# 07_FPGA_HSIO_B2.net
KiCad netlist of a schematic drawn in Altium Designer
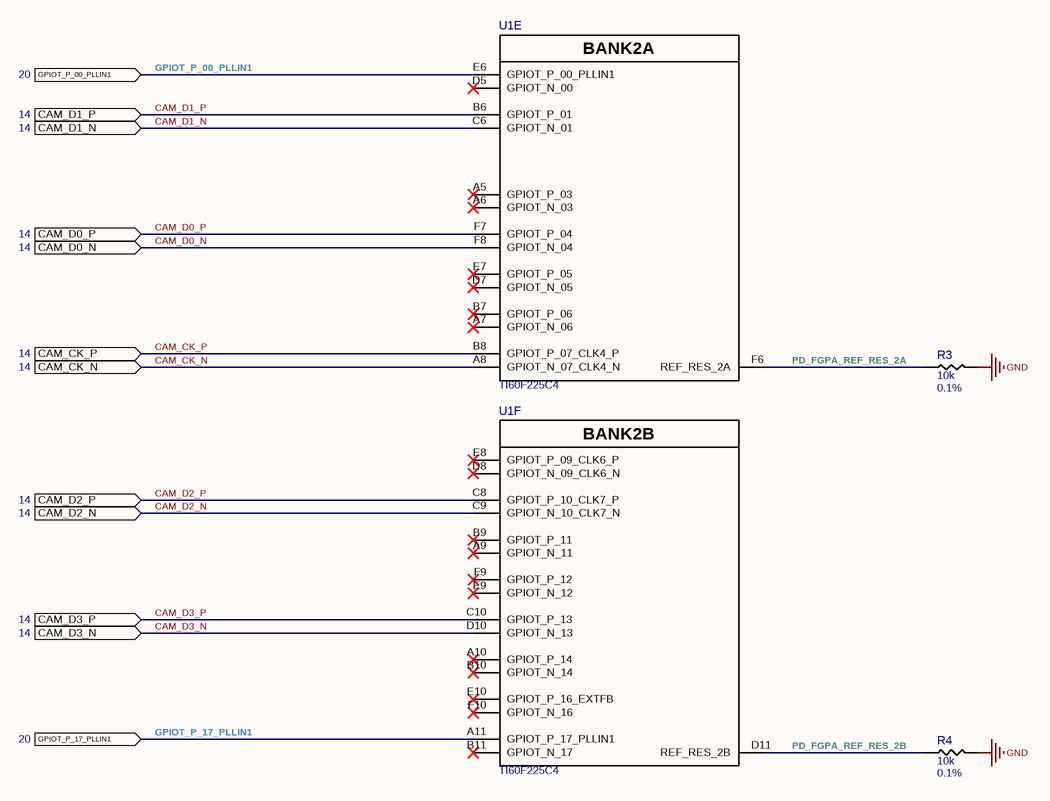
[diagram p0: 07_FPGA_HSIO_B2.SchDoc]

(export (version "E")
  (design (tool "Eeschema 10.0.6"))
  (components
    (comp (ref "R3")
      (value "10k")
      (footprint "RESC1005X03N")
      (description "RES SMD 10K OHM 0.1% 1/16W 0402")
      (fields (field (name "PART NUMBER") "RT0402BRD0710KL") (field (name "TOL") "0.1%"))
      (libsource (lib "Database") (part "Resistor_ENG"))
    )
    (comp (ref "R4")
      (value "10k")
      (footprint "RESC1005X03N")
      (description "RES SMD 10K OHM 0.1% 1/16W 0402")
      (fields (field (name "PART NUMBER") "RT0402BRD0710KL") (field (name "TOL") "0.1%"))
      (libsource (lib "Database") (part "Resistor_ENG"))
    )
    (comp (ref "U1")
      (value "TI60F225C4")
      (footprint "BGA225C65P15X15_1000X1000X100")
      (description "FPGA TITAN 140HSIO 4PLL 225BGA")
      (libsource (lib "Database") (part "TI60F225"))
    )
  )
  (nets
    (net (code "1") (name "/CAM_CK_N") (class "Default")
      (node (ref "U1") (pin "A8") (pinfunction "GPIOT_N_07_CLK4_N_A8") (pintype "passive"))
    )
    (net (code "2") (name "/CAM_CK_P") (class "Default")
      (node (ref "U1") (pin "B8") (pinfunction "GPIOT_P_07_CLK4_P_B8") (pintype "passive"))
    )
    (net (code "3") (name "/CAM_D0_N") (class "Default")
      (node (ref "U1") (pin "F8") (pinfunction "GPIOT_N_04_F8") (pintype "passive"))
    )
    (net (code "4") (name "/CAM_D0_P") (class "Default")
      (node (ref "U1") (pin "F7") (pinfunction "GPIOT_P_04_F7") (pintype "passive"))
    )
    (net (code "5") (name "/CAM_D1_N") (class "Default")
      (node (ref "U1") (pin "C6") (pinfunction "GPIOT_N_01_C6") (pintype "passive"))
    )
    (net (code "6") (name "/CAM_D1_P") (class "Default")
      (node (ref "U1") (pin "B6") (pinfunction "GPIOT_P_01_B6") (pintype "passive"))
    )
    (net (code "7") (name "/CAM_D2_N") (class "Default")
      (node (ref "U1") (pin "C9") (pinfunction "GPIOT_N_10_CLK7_N_C9") (pintype "passive"))
    )
    (net (code "8") (name "/CAM_D2_P") (class "Default")
      (node (ref "U1") (pin "C8") (pinfunction "GPIOT_P_10_CLK7_P_C8") (pintype "passive"))
    )
    (net (code "9") (name "/CAM_D3_N") (class "Default")
      (node (ref "U1") (pin "D10") (pinfunction "GPIOT_N_13_D10") (pintype "passive"))
    )
    (net (code "10") (name "/CAM_D3_P") (class "Default")
      (node (ref "U1") (pin "C10") (pinfunction "GPIOT_P_13_C10") (pintype "passive"))
    )
    (net (code "11") (name "/GPIOT_P_00_PLLIN1") (class "Default")
      (node (ref "U1") (pin "E6") (pinfunction "GPIOT_P_00_PLLIN1_E6") (pintype "passive"))
    )
    (net (code "12") (name "/GPIOT_P_17_PLLIN1") (class "Default")
      (node (ref "U1") (pin "A11") (pinfunction "GPIOT_P_17_PLLIN1_A11") (pintype "passive"))
    )
    (net (code "13") (name "/PD_FGPA_REF_RES_2A") (class "Default")
      (node (ref "R3") (pin "1") (pinfunction "1_1") (pintype "passive"))
      (node (ref "U1") (pin "F6") (pinfunction "REF_RES_2A_F6") (pintype "passive"))
    )
    (net (code "14") (name "/PD_FGPA_REF_RES_2B") (class "Default")
      (node (ref "R4") (pin "1") (pinfunction "1_1") (pintype "passive"))
      (node (ref "U1") (pin "D11") (pinfunction "REF_RES_2B_D11") (pintype "passive"))
    )
    (net (code "15") (name "GND") (class "Default")
      (node (ref "R3") (pin "2") (pinfunction "2_2") (pintype "passive"))
      (node (ref "R4") (pin "2") (pinfunction "2_2") (pintype "passive"))
    )
    (net (code "16") (name "unconnected-(U1E-GPIOT_N_00-PadD5)") (class "Default")
      (node (ref "U1") (pin "D5") (pinfunction "GPIOT_N_00_D5") (pintype "passive+no_connect"))
    )
    (net (code "17") (name "unconnected-(U1E-GPIOT_N_03-PadA6)") (class "Default")
      (node (ref "U1") (pin "A6") (pinfunction "GPIOT_N_03_A6") (pintype "passive+no_connect"))
    )
    (net (code "18") (name "unconnected-(U1E-GPIOT_N_05-PadD7)") (class "Default")
      (node (ref "U1") (pin "D7") (pinfunction "GPIOT_N_05_D7") (pintype "passive+no_connect"))
    )
    (net (code "19") (name "unconnected-(U1E-GPIOT_N_06-PadA7)") (class "Default")
      (node (ref "U1") (pin "A7") (pinfunction "GPIOT_N_06_A7") (pintype "passive+no_connect"))
    )
    (net (code "20") (name "unconnected-(U1E-GPIOT_P_03-PadA5)") (class "Default")
      (node (ref "U1") (pin "A5") (pinfunction "GPIOT_P_03_A5") (pintype "passive+no_connect"))
    )
    (net (code "21") (name "unconnected-(U1E-GPIOT_P_05-PadE7)") (class "Default")
      (node (ref "U1") (pin "E7") (pinfunction "GPIOT_P_05_E7") (pintype "passive+no_connect"))
    )
    (net (code "22") (name "unconnected-(U1E-GPIOT_P_06-PadB7)") (class "Default")
      (node (ref "U1") (pin "B7") (pinfunction "GPIOT_P_06_B7") (pintype "passive+no_connect"))
    )
    (net (code "23") (name "unconnected-(U1F-GPIOT_N_09_CLK6_N-PadD8)") (class "Default")
      (node (ref "U1") (pin "D8") (pinfunction "GPIOT_N_09_CLK6_N_D8") (pintype "passive+no_connect"))
    )
    (net (code "24") (name "unconnected-(U1F-GPIOT_N_11-PadA9)") (class "Default")
      (node (ref "U1") (pin "A9") (pinfunction "GPIOT_N_11_A9") (pintype "passive+no_connect"))
    )
    (net (code "25") (name "unconnected-(U1F-GPIOT_N_12-PadE9)") (class "Default")
      (node (ref "U1") (pin "E9") (pinfunction "GPIOT_N_12_E9") (pintype "passive+no_connect"))
    )
    (net (code "26") (name "unconnected-(U1F-GPIOT_N_14-PadB10)") (class "Default")
      (node (ref "U1") (pin "B10") (pinfunction "GPIOT_N_14_B10") (pintype "passive+no_connect"))
    )
    (net (code "27") (name "unconnected-(U1F-GPIOT_N_16-PadF10)") (class "Default")
      (node (ref "U1") (pin "F10") (pinfunction "GPIOT_N_16_F10") (pintype "passive+no_connect"))
    )
    (net (code "28") (name "unconnected-(U1F-GPIOT_N_17-PadB11)") (class "Default")
      (node (ref "U1") (pin "B11") (pinfunction "GPIOT_N_17_B11") (pintype "passive+no_connect"))
    )
    (net (code "29") (name "unconnected-(U1F-GPIOT_P_09_CLK6_P-PadE8)") (class "Default")
      (node (ref "U1") (pin "E8") (pinfunction "GPIOT_P_09_CLK6_P_E8") (pintype "passive+no_connect"))
    )
    (net (code "30") (name "unconnected-(U1F-GPIOT_P_11-PadB9)") (class "Default")
      (node (ref "U1") (pin "B9") (pinfunction "GPIOT_P_11_B9") (pintype "passive+no_connect"))
    )
    (net (code "31") (name "unconnected-(U1F-GPIOT_P_12-PadF9)") (class "Default")
      (node (ref "U1") (pin "F9") (pinfunction "GPIOT_P_12_F9") (pintype "passive+no_connect"))
    )
    (net (code "32") (name "unconnected-(U1F-GPIOT_P_14-PadA10)") (class "Default")
      (node (ref "U1") (pin "A10") (pinfunction "GPIOT_P_14_A10") (pintype "passive+no_connect"))
    )
    (net (code "33") (name "unconnected-(U1F-GPIOT_P_16_EXTFB-PadE10)") (class "Default")
      (node (ref "U1") (pin "E10") (pinfunction "GPIOT_P_16_EXTFB_E10") (pintype "passive+no_connect"))
    )
  )
)
